# DFP.net
KiCad netlist of a schematic drawn in Altium Designer
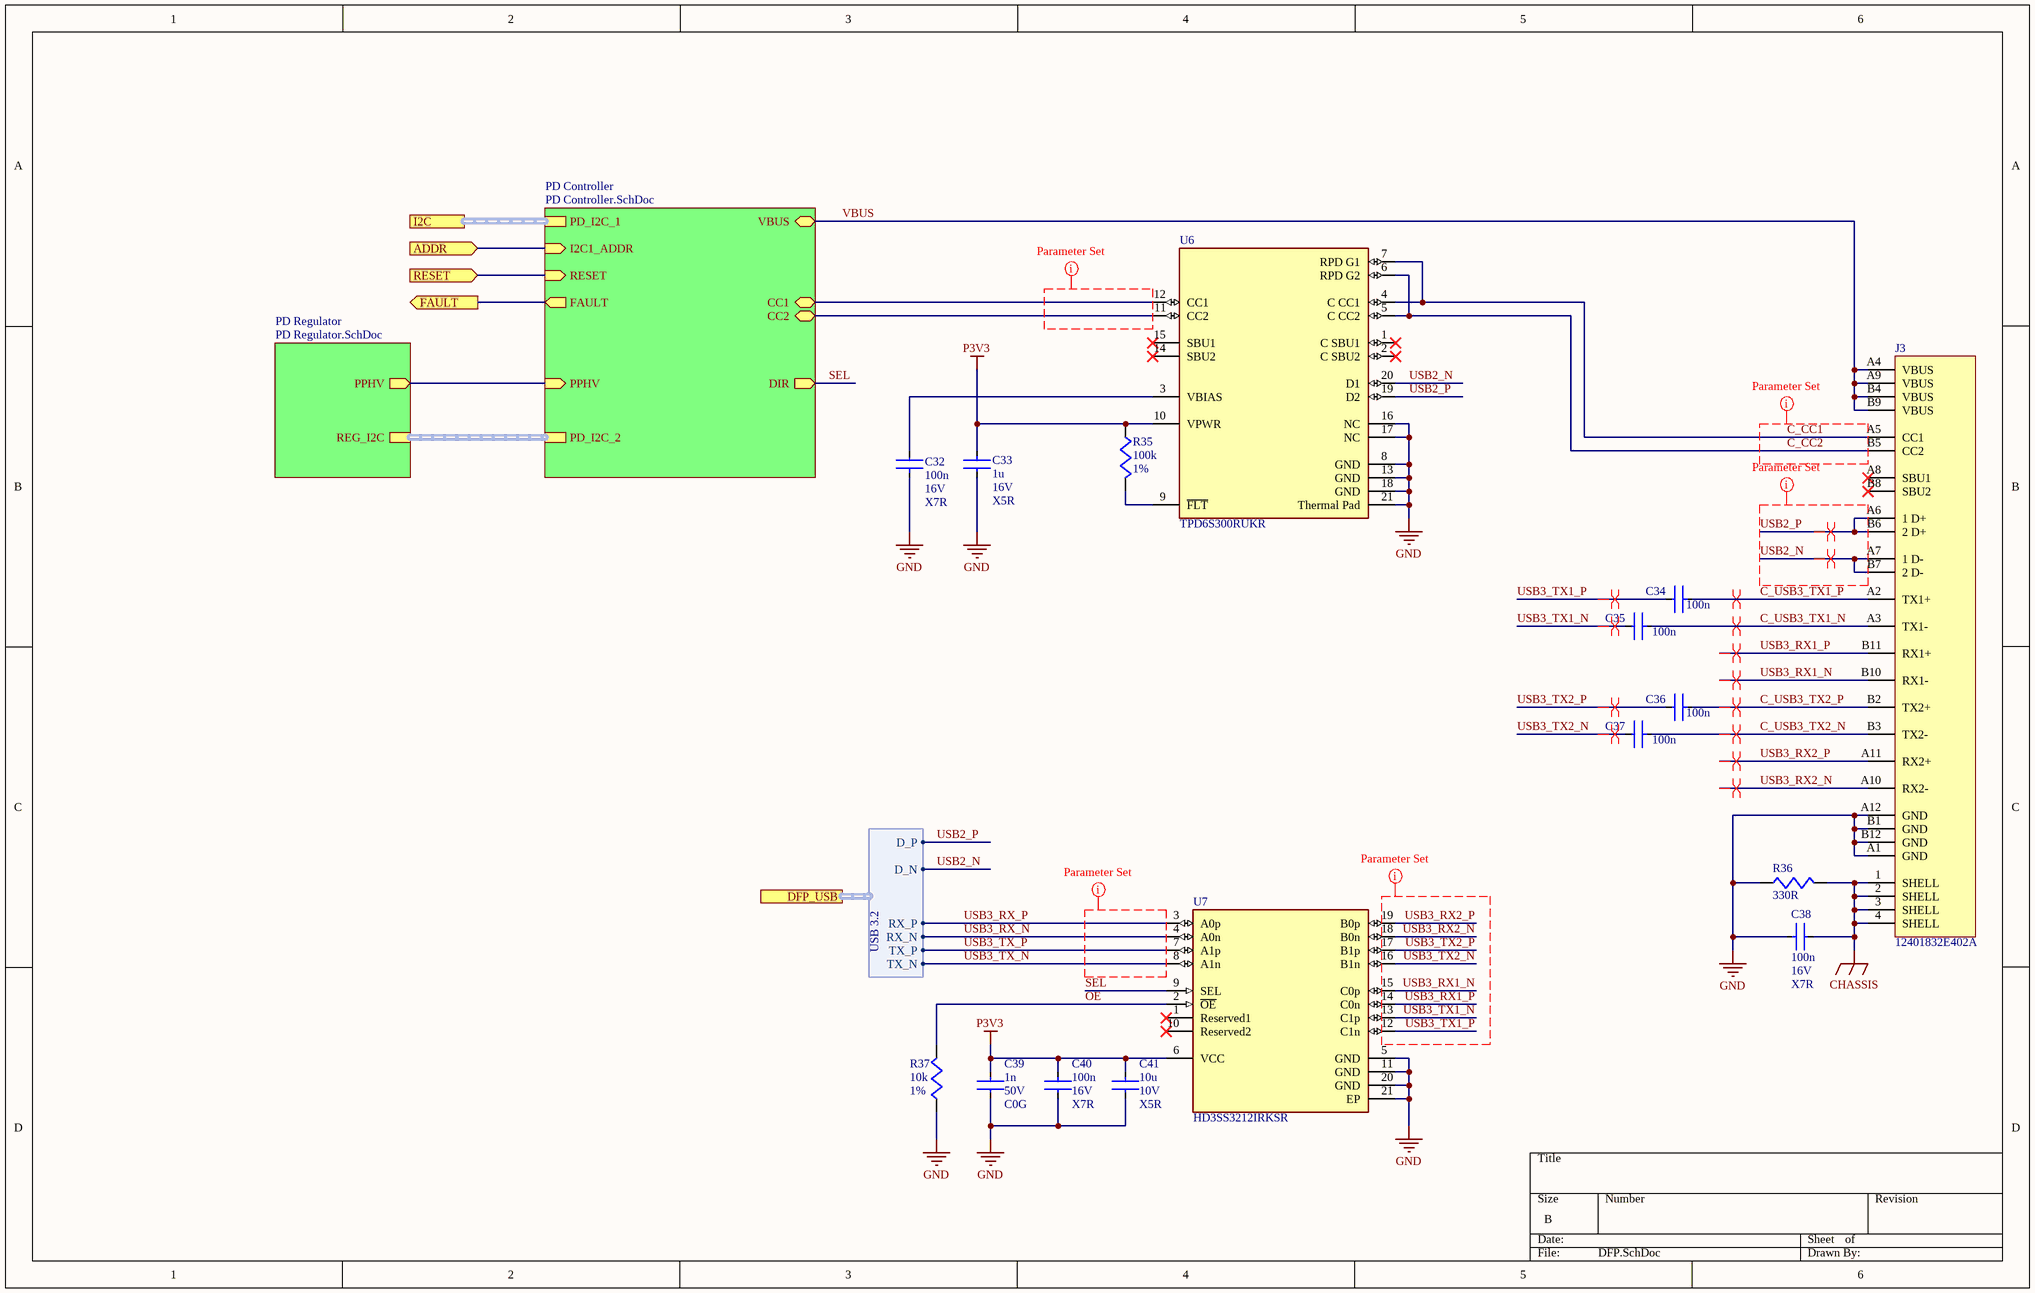
[diagram p0: DFP.SchDoc]

(export (version "E")
  (design (tool "Eeschema 10.0.6"))
  (components
    (comp (ref "C32")
      (value "100n")
      (footprint "CAPC1005X06N")
      (description "16V 100nF X7R ±10% 0402 Multilayer Ceramic Capacitors MLCC - SMD/SMT ROHS")
      (fields
        (field (name "VOLTAGE") "16V")
        (field (name "DIELECTRIC") "X7R")
        (field (name "LCSC PART #") "C1525")
        (field (name "Comment") "100nF 16V 0402")
      )
      (libsource (lib "CWRU Motorsports") (part "Capacitor"))
    )
    (comp (ref "C33")
      (value "1u")
      (footprint "CAPC1005X06N")
      (description "16V 1uF X5R ±10% 0402 Multilayer Ceramic Capacitors MLCC - SMD/SMT ROHS")
      (fields
        (field (name "VOLTAGE") "16V")
        (field (name "DIELECTRIC") "X5R")
        (field (name "LCSC PART #") "C29266")
        (field (name "Comment") "1uF 16V X5R 0402")
      )
      (libsource (lib "CWRU Motorsports") (part "Capacitor"))
    )
    (comp (ref "C34")
      (value "100n")
      (footprint "CAPC0603X03N")
      (description "10V 100nF X5R ±10% 0201 Multilayer Ceramic Capacitors MLCC - SMD/SMT ROHS")
      (fields (field (name "VOLTAGE") "10V") (field (name "LCSC PART #") "C76934"))
      (libsource (lib "CWRU Motorsports") (part "Capacitor"))
    )
    (comp (ref "C35")
      (value "100n")
      (footprint "CAPC0603X03N")
      (description "10V 100nF X5R ±10% 0201 Multilayer Ceramic Capacitors MLCC - SMD/SMT ROHS")
      (fields (field (name "VOLTAGE") "10V") (field (name "LCSC PART #") "C76934"))
      (libsource (lib "CWRU Motorsports") (part "Capacitor"))
    )
    (comp (ref "C36")
      (value "100n")
      (footprint "CAPC0603X03N")
      (description "10V 100nF X5R ±10% 0201 Multilayer Ceramic Capacitors MLCC - SMD/SMT ROHS")
      (fields (field (name "VOLTAGE") "10V") (field (name "LCSC PART #") "C76934"))
      (libsource (lib "CWRU Motorsports") (part "Capacitor"))
    )
    (comp (ref "C37")
      (value "100n")
      (footprint "CAPC0603X03N")
      (description "10V 100nF X5R ±10% 0201 Multilayer Ceramic Capacitors MLCC - SMD/SMT ROHS")
      (fields (field (name "VOLTAGE") "10V") (field (name "LCSC PART #") "C76934"))
      (libsource (lib "CWRU Motorsports") (part "Capacitor"))
    )
    (comp (ref "C38")
      (value "100n")
      (footprint "CAPC1005X06N")
      (description "16V 100nF X7R ±10% 0402 Multilayer Ceramic Capacitors MLCC - SMD/SMT ROHS")
      (fields
        (field (name "VOLTAGE") "16V")
        (field (name "DIELECTRIC") "X7R")
        (field (name "LCSC PART #") "C1525")
        (field (name "Comment") "100nF 16V 0402")
      )
      (libsource (lib "CWRU Motorsports") (part "Capacitor"))
    )
    (comp (ref "C39")
      (value "1n")
      (footprint "CAPC1608X08N")
      (description "C0G 1nF 50V ±5% 0603 Multilayer Ceramic Capacitors MLCC - SMD/SMT ROHS")
      (fields
        (field (name "VOLTAGE") "50V")
        (field (name "DIELECTRIC") "C0G")
        (field (name "LCSC PART #") "C342541")
        (field (name "Comment") "1nF C0G 0603")
      )
      (libsource (lib "CWRU Motorsports") (part "Capacitor"))
    )
    (comp (ref "C40")
      (value "100n")
      (footprint "CAPC1005X06N")
      (description "16V 100nF X7R ±10% 0402 Multilayer Ceramic Capacitors MLCC - SMD/SMT ROHS")
      (fields
        (field (name "VOLTAGE") "16V")
        (field (name "DIELECTRIC") "X7R")
        (field (name "LCSC PART #") "C1525")
        (field (name "Comment") "100nF 16V 0402")
      )
      (libsource (lib "CWRU Motorsports") (part "Capacitor"))
    )
    (comp (ref "C41")
      (value "10u")
      (footprint "CAPC1005X06N")
      (description "10uF 10V 0402 20% X5R CAP MLCC")
      (fields
        (field (name "VOLTAGE") "10V")
        (field (name "DIELECTRIC") "X5R")
        (field (name "LCSC PART #") "C527590")
        (field (name "Comment") "10uF 10V 0402")
      )
      (libsource (lib "CWRU Motorsports") (part "Capacitor"))
    )
    (comp (ref "J3")
      (value "12401832E402A")
      (footprint "FP-12401832E402A-MFG")
      (description "Conn USB Type C RCP 24 POS 0.25mm Solder RA SMD 24 Terminal 1 Port T/R")
      (fields (field (name "LCSC PART #") "C464604"))
      (libsource (lib "CWRU Motorsports") (part "50854493bfec571c3c083d899a0df29"))
    )
    (comp (ref "R35")
      (value "100k")
      (footprint "RESC1005X04M")
      (description "62.5mW Thick Film Resistors 50V ±100ppm/℃ ±1% 100kΩ 0402 Chip Resistor - Surface Mount ROHS")
      (fields
        (field (name "TOLERANCE") "1%")
        (field (name "LCSC PART #") "C60491")
        (field (name "Comment") "100k 1% 0402")
      )
      (libsource (lib "CWRU Motorsports") (part "Resistor"))
    )
    (comp (ref "R36")
      (value "330R")
      (footprint "RESC1005X04M")
      (description "62.5mW Thick Film Resistors 50V ±100ppm/℃ ±1% 330Ω 0402 Chip Resistor - Surface Mount ROHS")
      (fields (field (name "TOLERANCE") "1%") (field (name "LCSC PART #") "C105875"))
      (libsource (lib "CWRU Motorsports") (part "Resistor"))
    )
    (comp (ref "R37")
      (value "10k")
      (footprint "RESC1005X04M")
      (description "62.5mW Thick Film Resistors 50V ±100ppm/℃ ±1% 10kΩ 0402 Chip Resistor - Surface Mount ROHS")
      (fields
        (field (name "TOLERANCE") "1%")
        (field (name "LCSC PART #") "C60490")
        (field (name "Comment") "10k 1% 0402")
      )
      (libsource (lib "CWRU Motorsports") (part "Resistor"))
    )
    (comp (ref "U6")
      (value "TPD6S300RUKR")
      (footprint "FP-RUK0020B-MFG")
      (description "WQFN-20-EP(3x3) ESD and Surge Protection (TVS/ESD) ROHS")
      (fields (field (name "LCSC PART #") "C2649810"))
      (libsource (lib "CWRU Motorsports") (part "1ade46eb552870a5cb9a85cf5497b7f"))
    )
    (comp (ref "U7")
      (value "HD3SS3212IRKSR")
      (footprint "FP-RKS0020A-MFG")
      (description "2-channel 10-Gbps 2: 1/1: 2 USB 3.1 differential mux/demux 20-VQFN -40 to 85")
      (libsource (lib "CWRU Motorsports") (part "6af698f8cd084955c503da06e1ea90e"))
    )
  )
  (nets
    (net (code "5") (name "/CC1") (class "Default")
      (node (ref "U6") (pin "12") (pinfunction "CC1_12") (pintype "bidirectional"))
    )
    (net (code "6") (name "/CC2") (class "Default")
      (node (ref "U6") (pin "11") (pinfunction "CC2_11") (pintype "bidirectional"))
    )
    (net (code "7") (name "/C_CC1") (class "Default")
      (node (ref "J3") (pin "A5") (pinfunction "CC1_A5") (pintype "power_in"))
      (node (ref "U6") (pin "4") (pinfunction "C_CC1_4") (pintype "bidirectional"))
      (node (ref "U6") (pin "7") (pinfunction "RPD_G1_7") (pintype "bidirectional"))
    )
    (net (code "8") (name "/C_CC2") (class "Default")
      (node (ref "J3") (pin "B5") (pinfunction "CC2_B5") (pintype "power_in"))
      (node (ref "U6") (pin "5") (pinfunction "C_CC2_5") (pintype "bidirectional"))
      (node (ref "U6") (pin "6") (pinfunction "RPD_G2_6") (pintype "bidirectional"))
    )
    (net (code "9") (name "/C_USB3_TX1_N") (class "Default")
      (node (ref "C35") (pin "1") (pinfunction "1_1") (pintype "passive"))
      (node (ref "J3") (pin "A3") (pinfunction "TX1-_A3") (pintype "passive"))
    )
    (net (code "10") (name "/C_USB3_TX1_P") (class "Default")
      (node (ref "C34") (pin "1") (pinfunction "1_1") (pintype "passive"))
      (node (ref "J3") (pin "A2") (pinfunction "TX1+_A2") (pintype "passive"))
    )
    (net (code "11") (name "/C_USB3_TX2_N") (class "Default")
      (node (ref "C37") (pin "1") (pinfunction "1_1") (pintype "passive"))
      (node (ref "J3") (pin "B3") (pinfunction "TX2-_B3") (pintype "passive"))
    )
    (net (code "12") (name "/C_USB3_TX2_P") (class "Default")
      (node (ref "C36") (pin "1") (pinfunction "1_1") (pintype "passive"))
      (node (ref "J3") (pin "B2") (pinfunction "TX2+_B2") (pintype "passive"))
    )
    (net (code "15") (name "/OE") (class "Default")
      (node (ref "R37") (pin "2") (pinfunction "2_2") (pintype "passive"))
      (node (ref "U7") (pin "2") (pinfunction "~{OE}_2") (pintype "input"))
    )
    (net (code "19") (name "/SEL") (class "Default")
      (node (ref "U7") (pin "9") (pinfunction "SEL_9") (pintype "input"))
    )
    (net (code "20") (name "/USB2_N") (class "Default")
      (node (ref "J3") (pin "A7") (pinfunction "1_D-_A7") (pintype "passive"))
      (node (ref "J3") (pin "B7") (pinfunction "2_D-_B7") (pintype "passive"))
      (node (ref "U6") (pin "20") (pinfunction "D1_20") (pintype "bidirectional"))
    )
    (net (code "21") (name "/USB2_P") (class "Default")
      (node (ref "J3") (pin "A6") (pinfunction "1_D+_A6") (pintype "passive"))
      (node (ref "J3") (pin "B6") (pinfunction "2_D+_B6") (pintype "passive"))
      (node (ref "U6") (pin "19") (pinfunction "D2_19") (pintype "bidirectional"))
    )
    (net (code "22") (name "/USB3_RX1_N") (class "Default")
      (node (ref "J3") (pin "B10") (pinfunction "RX1-_B10") (pintype "power_in"))
      (node (ref "U7") (pin "15") (pinfunction "C0p_15") (pintype "bidirectional"))
    )
    (net (code "23") (name "/USB3_RX1_P") (class "Default")
      (node (ref "J3") (pin "B11") (pinfunction "RX1+_B11") (pintype "power_in"))
      (node (ref "U7") (pin "14") (pinfunction "C0n_14") (pintype "bidirectional"))
    )
    (net (code "24") (name "/USB3_RX2_N") (class "Default")
      (node (ref "J3") (pin "A10") (pinfunction "RX2-_A10") (pintype "passive"))
      (node (ref "U7") (pin "18") (pinfunction "B0n_18") (pintype "bidirectional"))
    )
    (net (code "25") (name "/USB3_RX2_P") (class "Default")
      (node (ref "J3") (pin "A11") (pinfunction "RX2+_A11") (pintype "passive"))
      (node (ref "U7") (pin "19") (pinfunction "B0p_19") (pintype "bidirectional"))
    )
    (net (code "26") (name "/USB3_RX_N") (class "Default")
      (node (ref "U7") (pin "4") (pinfunction "A0n_4") (pintype "bidirectional"))
    )
    (net (code "27") (name "/USB3_RX_P") (class "Default")
      (node (ref "U7") (pin "3") (pinfunction "A0p_3") (pintype "bidirectional"))
    )
    (net (code "28") (name "/USB3_TX1_N") (class "Default")
      (node (ref "C35") (pin "2") (pinfunction "2_2") (pintype "passive"))
      (node (ref "U7") (pin "13") (pinfunction "C1p_13") (pintype "bidirectional"))
    )
    (net (code "29") (name "/USB3_TX1_P") (class "Default")
      (node (ref "C34") (pin "2") (pinfunction "2_2") (pintype "passive"))
      (node (ref "U7") (pin "12") (pinfunction "C1n_12") (pintype "bidirectional"))
    )
    (net (code "30") (name "/USB3_TX2_N") (class "Default")
      (node (ref "C37") (pin "2") (pinfunction "2_2") (pintype "passive"))
      (node (ref "U7") (pin "16") (pinfunction "B1n_16") (pintype "bidirectional"))
    )
    (net (code "31") (name "/USB3_TX2_P") (class "Default")
      (node (ref "C36") (pin "2") (pinfunction "2_2") (pintype "passive"))
      (node (ref "U7") (pin "17") (pinfunction "B1p_17") (pintype "bidirectional"))
    )
    (net (code "32") (name "/USB3_TX_N") (class "Default")
      (node (ref "U7") (pin "8") (pinfunction "A1n_8") (pintype "bidirectional"))
    )
    (net (code "33") (name "/USB3_TX_P") (class "Default")
      (node (ref "U7") (pin "7") (pinfunction "A1p_7") (pintype "bidirectional"))
    )
    (net (code "34") (name "/VBUS") (class "Default")
      (node (ref "J3") (pin "A4") (pinfunction "VBUS_A4") (pintype "passive"))
      (node (ref "J3") (pin "A9") (pinfunction "VBUS_A9") (pintype "power_in"))
      (node (ref "J3") (pin "B4") (pinfunction "VBUS_B4") (pintype "passive"))
      (node (ref "J3") (pin "B9") (pinfunction "VBUS_B9") (pintype "power_in"))
    )
    (net (code "36") (name "CHASSIS") (class "Default")
      (node (ref "C38") (pin "2") (pinfunction "2_2") (pintype "passive"))
      (node (ref "J3") (pin "1") (pinfunction "SHELL_1") (pintype "power_in"))
      (node (ref "J3") (pin "2") (pinfunction "SHELL_2") (pintype "passive"))
      (node (ref "J3") (pin "3") (pinfunction "SHELL_3") (pintype "passive"))
      (node (ref "J3") (pin "4") (pinfunction "SHELL_4") (pintype "power_in"))
      (node (ref "R36") (pin "1") (pinfunction "1_1") (pintype "passive"))
    )
    (net (code "37") (name "GND") (class "Default")
      (node (ref "C32") (pin "1") (pinfunction "1_1") (pintype "passive"))
      (node (ref "C33") (pin "2") (pinfunction "2_2") (pintype "passive"))
      (node (ref "C38") (pin "1") (pinfunction "1_1") (pintype "passive"))
      (node (ref "C39") (pin "2") (pinfunction "2_2") (pintype "passive"))
      (node (ref "C40") (pin "2") (pinfunction "2_2") (pintype "passive"))
      (node (ref "C41") (pin "2") (pinfunction "2_2") (pintype "passive"))
      (node (ref "J3") (pin "A1") (pinfunction "GND_A1") (pintype "passive"))
      (node (ref "J3") (pin "A12") (pinfunction "GND_A12") (pintype "power_in"))
      (node (ref "J3") (pin "B1") (pinfunction "GND_B1") (pintype "passive"))
      (node (ref "J3") (pin "B12") (pinfunction "GND_B12") (pintype "power_in"))
      (node (ref "R36") (pin "2") (pinfunction "2_2") (pintype "passive"))
      (node (ref "R37") (pin "1") (pinfunction "1_1") (pintype "passive"))
      (node (ref "U6") (pin "13") (pinfunction "GND_13") (pintype "power_in"))
      (node (ref "U6") (pin "16") (pinfunction "NC_16") (pintype "passive"))
      (node (ref "U6") (pin "17") (pinfunction "NC_17") (pintype "passive"))
      (node (ref "U6") (pin "18") (pinfunction "GND_18") (pintype "power_in"))
      (node (ref "U6") (pin "21") (pinfunction "Thermal_Pad_21") (pintype "power_in"))
      (node (ref "U6") (pin "8") (pinfunction "GND_8") (pintype "power_in"))
      (node (ref "U7") (pin "11") (pinfunction "GND_11") (pintype "power_in"))
      (node (ref "U7") (pin "20") (pinfunction "GND_20") (pintype "power_in"))
      (node (ref "U7") (pin "21") (pinfunction "EP_21") (pintype "power_in"))
      (node (ref "U7") (pin "5") (pinfunction "GND_5") (pintype "power_in"))
    )
    (net (code "38") (name "Net-(U6-VBIAS)") (class "Default")
      (node (ref "C32") (pin "2") (pinfunction "2_2") (pintype "passive"))
      (node (ref "U6") (pin "3") (pinfunction "VBIAS_3") (pintype "passive"))
    )
    (net (code "39") (name "Net-(U6-~{FLT})") (class "Default")
      (node (ref "R35") (pin "2") (pinfunction "2_2") (pintype "passive"))
      (node (ref "U6") (pin "9") (pinfunction "~{FLT}_9") (pintype "open_collector"))
    )
    (net (code "40") (name "P3V3") (class "Default")
      (node (ref "C33") (pin "1") (pinfunction "1_1") (pintype "passive"))
      (node (ref "C39") (pin "1") (pinfunction "1_1") (pintype "passive"))
      (node (ref "C40") (pin "1") (pinfunction "1_1") (pintype "passive"))
      (node (ref "C41") (pin "1") (pinfunction "1_1") (pintype "passive"))
      (node (ref "R35") (pin "1") (pinfunction "1_1") (pintype "passive"))
      (node (ref "U6") (pin "10") (pinfunction "VPWR_10") (pintype "power_in"))
      (node (ref "U7") (pin "6") (pinfunction "VCC_6") (pintype "power_in"))
    )
    (net (code "41") (name "unconnected-(J3-SBU1-PadA8)") (class "Default")
      (node (ref "J3") (pin "A8") (pinfunction "SBU1_A8") (pintype "power_in+no_connect"))
    )
    (net (code "42") (name "unconnected-(J3-SBU2-PadB8)") (class "Default")
      (node (ref "J3") (pin "B8") (pinfunction "SBU2_B8") (pintype "power_in+no_connect"))
    )
    (net (code "43") (name "unconnected-(U6-C_SBU1-Pad1)") (class "Default")
      (node (ref "U6") (pin "1") (pinfunction "C_SBU1_1") (pintype "bidirectional+no_connect"))
    )
    (net (code "44") (name "unconnected-(U6-C_SBU2-Pad2)") (class "Default")
      (node (ref "U6") (pin "2") (pinfunction "C_SBU2_2") (pintype "bidirectional+no_connect"))
    )
    (net (code "45") (name "unconnected-(U6-SBU1-Pad15)") (class "Default")
      (node (ref "U6") (pin "15") (pinfunction "SBU1_15") (pintype "passive+no_connect"))
    )
    (net (code "46") (name "unconnected-(U6-SBU2-Pad14)") (class "Default")
      (node (ref "U6") (pin "14") (pinfunction "SBU2_14") (pintype "passive+no_connect"))
    )
    (net (code "47") (name "unconnected-(U7-Reserved1-Pad1)") (class "Default")
      (node (ref "U7") (pin "1") (pinfunction "Reserved1_1") (pintype "passive+no_connect"))
    )
    (net (code "48") (name "unconnected-(U7-Reserved2-Pad10)") (class "Default")
      (node (ref "U7") (pin "10") (pinfunction "Reserved2_10") (pintype "passive+no_connect"))
    )
  )
)
